# medusa-AI-sensors.net
KiCad netlist of a schematic drawn in Altium Designer
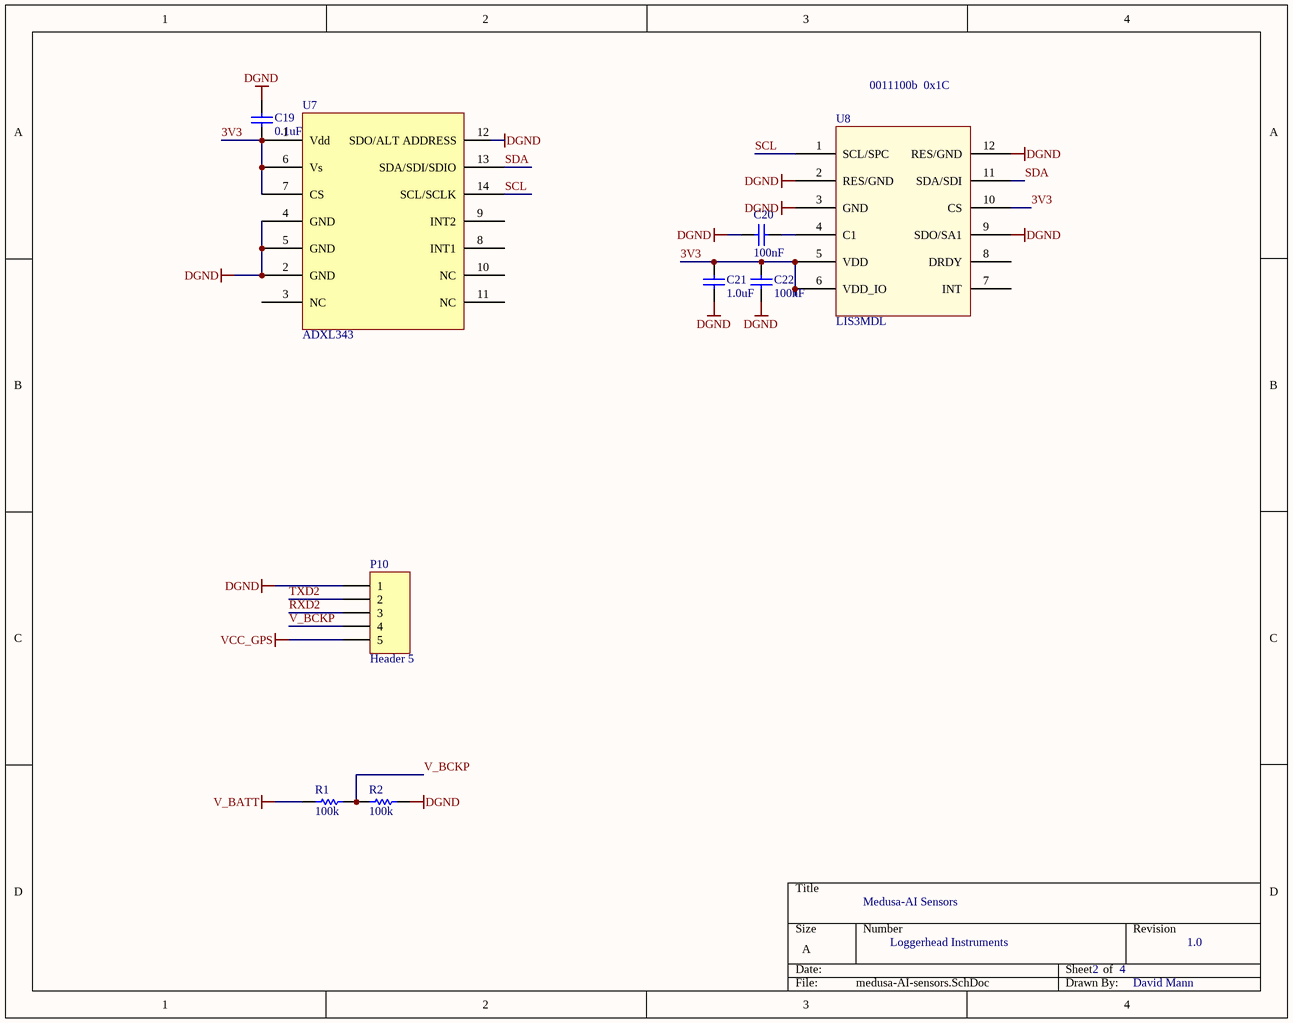
[diagram p0: medusa-AI-sensors.SchDoc]

(export (version "E")
  (design (tool "Eeschema 10.0.6"))
  (components
    (comp (ref "C19")
      (value "0.1uF")
      (footprint "0402")
      (description "Ceramic Chip Capacitor - Standard")
      (fields (field (name "PUBLISHER") "Altium Limited"))
      (libsource (lib "KEMET Chip Capacitor") (part "C0402"))
    )
    (comp (ref "C20")
      (value "100nF")
      (footprint "0402")
      (description "Ceramic Chip Capacitor - Standard")
      (fields (field (name "PUBLISHER") "Altium Limited"))
      (libsource (lib "KEMET Chip Capacitor") (part "C0402"))
    )
    (comp (ref "C21")
      (value "1.0uF")
      (footprint "0402")
      (description "Ceramic Chip Capacitor - Standard")
      (fields (field (name "PUBLISHER") "Altium Limited"))
      (libsource (lib "KEMET Chip Capacitor") (part "C0402"))
    )
    (comp (ref "C22")
      (value "100nF")
      (footprint "0402")
      (description "Ceramic Chip Capacitor - Standard")
      (fields (field (name "PUBLISHER") "Altium Limited"))
      (libsource (lib "KEMET Chip Capacitor") (part "C0402"))
    )
    (comp (ref "P10")
      (value "Header 5")
      (footprint "HDR1X5")
      (description "Header, 5-Pin")
      (fields (field (name "PUBLISHER") "Altium Limited"))
      (libsource (lib "Miscellaneous Connectors") (part "Header 5"))
    )
    (comp (ref "R1")
      (value "100k")
      (footprint "3-0603")
      (fields (field (name "PUBLISHER") "Altium Limited"))
      (libsource (lib "Panasonic Resistor") (part "ERJ3RK"))
    )
    (comp (ref "R2")
      (value "100k")
      (footprint "3-0603")
      (fields (field (name "PUBLISHER") "Altium Limited"))
      (libsource (lib "Panasonic Resistor") (part "ERJ3RK"))
    )
    (comp (ref "U7") (value "ADXL343") (footprint "ADXL345") (libsource (lib "Loggerhead") (part "ADXL345")))
    (comp (ref "U8")
      (value "LIS3MDL")
      (footprint "LGA-12")
      (description "magnetometer")
      (libsource (lib "Loggerhead") (part "LIS3MDL"))
    )
  )
  (nets
    (net (code "1") (name "/3V3") (class "Default")
      (node (ref "C19") (pin "1") (pinfunction "1_1") (pintype "passive"))
      (node (ref "C21") (pin "1") (pinfunction "1_1") (pintype "passive"))
      (node (ref "C22") (pin "1") (pinfunction "1_1") (pintype "passive"))
      (node (ref "U7") (pin "1") (pinfunction "Vdd_1") (pintype "power_in"))
      (node (ref "U7") (pin "6") (pinfunction "Vs_6") (pintype "passive"))
      (node (ref "U7") (pin "7") (pinfunction "CS_7") (pintype "passive"))
      (node (ref "U8") (pin "10") (pinfunction "CS_10") (pintype "passive"))
      (node (ref "U8") (pin "5") (pinfunction "VDD_5") (pintype "passive"))
      (node (ref "U8") (pin "6") (pinfunction "VDD_IO_6") (pintype "passive"))
    )
    (net (code "2") (name "/RXD2") (class "Default")
      (node (ref "P10") (pin "3") (pinfunction "3_3") (pintype "passive"))
    )
    (net (code "3") (name "/SCL") (class "Default")
      (node (ref "U7") (pin "14") (pinfunction "SCL/SCLK_14") (pintype "passive"))
      (node (ref "U8") (pin "1") (pinfunction "SCL/SPC_1") (pintype "passive"))
    )
    (net (code "4") (name "/SDA") (class "Default")
      (node (ref "U7") (pin "13") (pinfunction "SDA/SDI/SDIO_13") (pintype "passive"))
      (node (ref "U8") (pin "11") (pinfunction "SDA/SDI_11") (pintype "passive"))
    )
    (net (code "5") (name "/TXD2") (class "Default")
      (node (ref "P10") (pin "2") (pinfunction "2_2") (pintype "passive"))
    )
    (net (code "6") (name "/V_BCKP") (class "Default")
      (node (ref "P10") (pin "4") (pinfunction "4_4") (pintype "passive"))
      (node (ref "R1") (pin "1") (pinfunction "1_1") (pintype "passive"))
      (node (ref "R2") (pin "2") (pinfunction "2_2") (pintype "passive"))
    )
    (net (code "7") (name "DGND") (class "Default")
      (node (ref "C19") (pin "2") (pinfunction "2_2") (pintype "passive"))
      (node (ref "C20") (pin "1") (pinfunction "1_1") (pintype "passive"))
      (node (ref "C21") (pin "2") (pinfunction "2_2") (pintype "passive"))
      (node (ref "C22") (pin "2") (pinfunction "2_2") (pintype "passive"))
      (node (ref "P10") (pin "1") (pinfunction "1_1") (pintype "passive"))
      (node (ref "R2") (pin "1") (pinfunction "1_1") (pintype "passive"))
      (node (ref "U7") (pin "12") (pinfunction "SDO/ALT_ADDRESS_12") (pintype "passive"))
      (node (ref "U7") (pin "2") (pinfunction "GND_2") (pintype "passive"))
      (node (ref "U7") (pin "4") (pinfunction "GND_4") (pintype "passive"))
      (node (ref "U7") (pin "5") (pinfunction "GND_5") (pintype "passive"))
      (node (ref "U8") (pin "12") (pinfunction "RES/GND_12") (pintype "passive"))
      (node (ref "U8") (pin "2") (pinfunction "RES/GND_2") (pintype "passive"))
      (node (ref "U8") (pin "3") (pinfunction "GND_3") (pintype "passive"))
      (node (ref "U8") (pin "9") (pinfunction "SDO/SA1_9") (pintype "passive"))
    )
    (net (code "8") (name "Net-(U8-C1)") (class "Default")
      (node (ref "C20") (pin "2") (pinfunction "2_2") (pintype "passive"))
      (node (ref "U8") (pin "4") (pinfunction "C1_4") (pintype "passive"))
    )
    (net (code "9") (name "VCC_GPS") (class "Default")
      (node (ref "P10") (pin "5") (pinfunction "5_5") (pintype "passive"))
    )
    (net (code "10") (name "V_BATT") (class "Default")
      (node (ref "R1") (pin "2") (pinfunction "2_2") (pintype "passive"))
    )
    (net (code "11") (name "unconnected-(U7-INT1-Pad8)") (class "Default")
      (node (ref "U7") (pin "8") (pinfunction "INT1_8") (pintype "passive"))
    )
    (net (code "12") (name "unconnected-(U7-INT2-Pad9)") (class "Default")
      (node (ref "U7") (pin "9") (pinfunction "INT2_9") (pintype "passive"))
    )
    (net (code "13") (name "unconnected-(U7-NC-Pad3)") (class "Default")
      (node (ref "U7") (pin "3") (pinfunction "NC_3") (pintype "passive"))
    )
    (net (code "14") (name "unconnected-(U7-NC-Pad10)") (class "Default")
      (node (ref "U7") (pin "10") (pinfunction "NC_10") (pintype "passive"))
    )
    (net (code "15") (name "unconnected-(U7-NC-Pad11)") (class "Default")
      (node (ref "U7") (pin "11") (pinfunction "NC_11") (pintype "passive"))
    )
    (net (code "16") (name "unconnected-(U8-DRDY-Pad8)") (class "Default")
      (node (ref "U8") (pin "8") (pinfunction "DRDY_8") (pintype "passive"))
    )
    (net (code "17") (name "unconnected-(U8-INT-Pad7)") (class "Default")
      (node (ref "U8") (pin "7") (pinfunction "INT_7") (pintype "passive"))
    )
  )
)
